# AutoBlinds.net
KiCad netlist of a schematic drawn in EAGLE
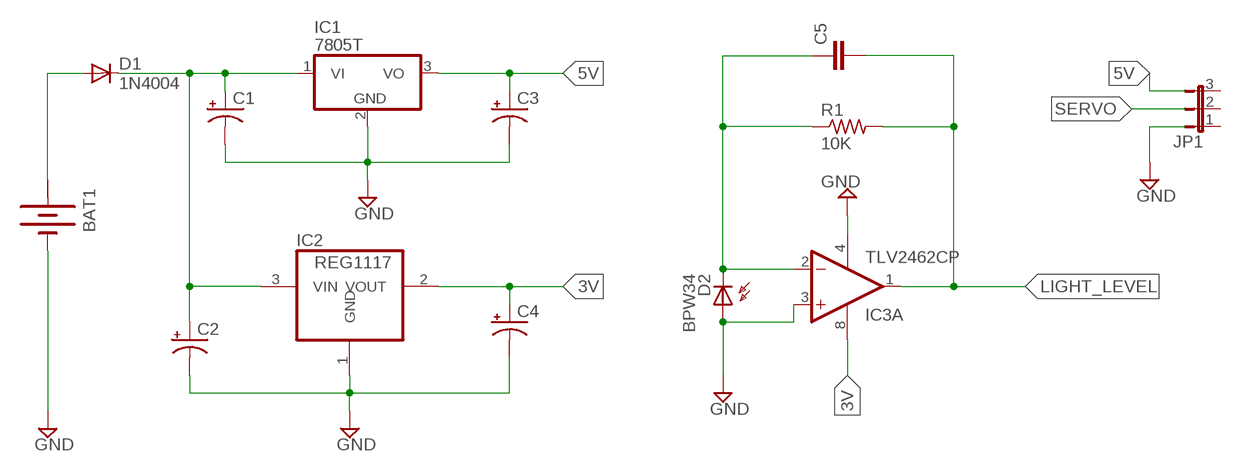
[diagram p0: schematic, sheet 1]

(export (version "E")
  (design (tool "Eeschema 10.0.6"))
  (components
    (comp (ref "BAT1")
      (value "BATTERY")
      (footprint "eagle-import:BATTERY")
      (libsource (lib "eagle-import") (part "BATTERY"))
    )
    (comp (ref "C1")
      (value "CPOL-USE3.5-10")
      (footprint "eagle-import:E3,5-10")
      (libsource (lib "eagle-import") (part "CPOL-USE3.5-10"))
    )
    (comp (ref "C2")
      (value "CPOL-USE3.5-10")
      (footprint "eagle-import:E3,5-10")
      (libsource (lib "eagle-import") (part "CPOL-USE3.5-10"))
    )
    (comp (ref "C3")
      (value "CPOL-USE3.5-10")
      (footprint "eagle-import:E3,5-10")
      (libsource (lib "eagle-import") (part "CPOL-USE3.5-10"))
    )
    (comp (ref "C4")
      (value "CPOL-USE3.5-10")
      (footprint "eagle-import:E3,5-10")
      (libsource (lib "eagle-import") (part "CPOL-USE3.5-10"))
    )
    (comp (ref "C5")
      (value "CAPPTH1")
      (footprint "eagle-import:CAP-PTH-5MM")
      (libsource (lib "eagle-import") (part "CAPPTH1"))
    )
    (comp (ref "D1")
      (value "1N4004")
      (footprint "eagle-import:DO41-10")
      (libsource (lib "eagle-import") (part "1N4004"))
    )
    (comp (ref "D2")
      (value "BPW34")
      (footprint "eagle-import:BPW32")
      (libsource (lib "eagle-import") (part "BPW32"))
    )
    (comp (ref "IC1")
      (value "7805T")
      (footprint "eagle-import:TO220H")
      (libsource (lib "eagle-import") (part "78T05"))
    )
    (comp (ref "IC2")
      (value "REG1117")
      (footprint "eagle-import:SOT223")
      (libsource (lib "eagle-import") (part "REG1117"))
    )
    (comp (ref "IC3")
      (value "TLV2462CP")
      (footprint "eagle-import:DIL08")
      (libsource (lib "eagle-import") (part "OPA2PA134"))
    )
    (comp (ref "JP1")
      (value "JP2W")
      (footprint "eagle-import:JP2W")
      (libsource (lib "eagle-import") (part "JP2W"))
    )
    (comp (ref "R1")
      (value "10K")
      (footprint "eagle-import:0204_7")
      (libsource (lib "eagle-import") (part "R-US_0204/7"))
    )
  )
  (nets
    (net (code "1") (name "/+") (class "Default")
      (node (ref "BAT1") (pin "+@1") (pinfunction "+_+@1") (pintype "power_in"))
    )
    (net (code "2") (name "3V") (class "Default")
      (node (ref "C4") (pin "+") (pinfunction "+_+") (pintype "passive"))
      (node (ref "IC2") (pin "2") (pinfunction "VOUT_2") (pintype "output"))
      (node (ref "IC3") (pin "8") (pinfunction "V+_8") (pintype "power_in"))
    )
    (net (code "3") (name "5V") (class "Default")
      (node (ref "C3") (pin "+") (pinfunction "+_+") (pintype "passive"))
      (node (ref "IC1") (pin "3") (pinfunction "VO_3") (pintype "passive"))
    )
    (net (code "4") (name "GND") (class "Default")
      (node (ref "BAT1") (pin "-") (pinfunction "-_-") (pintype "power_in"))
      (node (ref "C1") (pin "-") (pinfunction "-_-") (pintype "passive"))
      (node (ref "C2") (pin "-") (pinfunction "-_-") (pintype "passive"))
      (node (ref "C3") (pin "-") (pinfunction "-_-") (pintype "passive"))
      (node (ref "C4") (pin "-") (pinfunction "-_-") (pintype "passive"))
      (node (ref "D2") (pin "A") (pinfunction "A_A") (pintype "passive"))
      (node (ref "IC1") (pin "2") (pinfunction "GND_2") (pintype "passive"))
      (node (ref "IC2") (pin "1") (pinfunction "GND_1") (pintype "power_in"))
      (node (ref "IC3") (pin "3") (pinfunction "+IN_3") (pintype "input"))
      (node (ref "IC3") (pin "4") (pinfunction "V-_4") (pintype "power_in"))
    )
    (net (code "5") (name "LIGHT_LEVEL") (class "Default")
      (node (ref "C5") (pin "2") (pinfunction "2_2") (pintype "passive"))
      (node (ref "IC3") (pin "1") (pinfunction "OUT_1") (pintype "output"))
      (node (ref "R1") (pin "2") (pinfunction "2_2") (pintype "passive"))
    )
    (net (code "6") (name "Net-(BAT1-Pad+)") (class "Default")
      (node (ref "BAT1") (pin "+") (pinfunction "+_+") (pintype "power_in"))
      (node (ref "D1") (pin "A") (pinfunction "A_A") (pintype "passive"))
    )
    (net (code "7") (name "Net-(D2-C)") (class "Default")
      (node (ref "C5") (pin "1") (pinfunction "1_1") (pintype "passive"))
      (node (ref "D2") (pin "K") (pinfunction "C_K") (pintype "passive"))
      (node (ref "IC3") (pin "2") (pinfunction "-IN_2") (pintype "input"))
      (node (ref "R1") (pin "1") (pinfunction "1_1") (pintype "passive"))
    )
    (net (code "8") (name "Net-(IC1-VI)") (class "Default")
      (node (ref "C1") (pin "+") (pinfunction "+_+") (pintype "passive"))
      (node (ref "C2") (pin "+") (pinfunction "+_+") (pintype "passive"))
      (node (ref "D1") (pin "C") (pinfunction "C_C") (pintype "passive"))
      (node (ref "IC1") (pin "1") (pinfunction "VI_1") (pintype "input"))
      (node (ref "IC2") (pin "3") (pinfunction "VIN_3") (pintype "input"))
    )
    (net (code "10") (name "unconnected-(JP1-Pad1)") (class "Default")
      (node (ref "JP1") (pin "1") (pinfunction "1_1") (pintype "passive"))
    )
    (net (code "11") (name "unconnected-(JP1-Pad2)") (class "Default")
      (node (ref "JP1") (pin "2") (pinfunction "2_2") (pintype "passive"))
    )
    (net (code "12") (name "unconnected-(JP1-Pad3)") (class "Default")
      (node (ref "JP1") (pin "3") (pinfunction "3_3") (pintype "passive"))
    )
  )
)
